# Sheet1_3big.net
KiCad netlist of a schematic drawn in Altium Designer
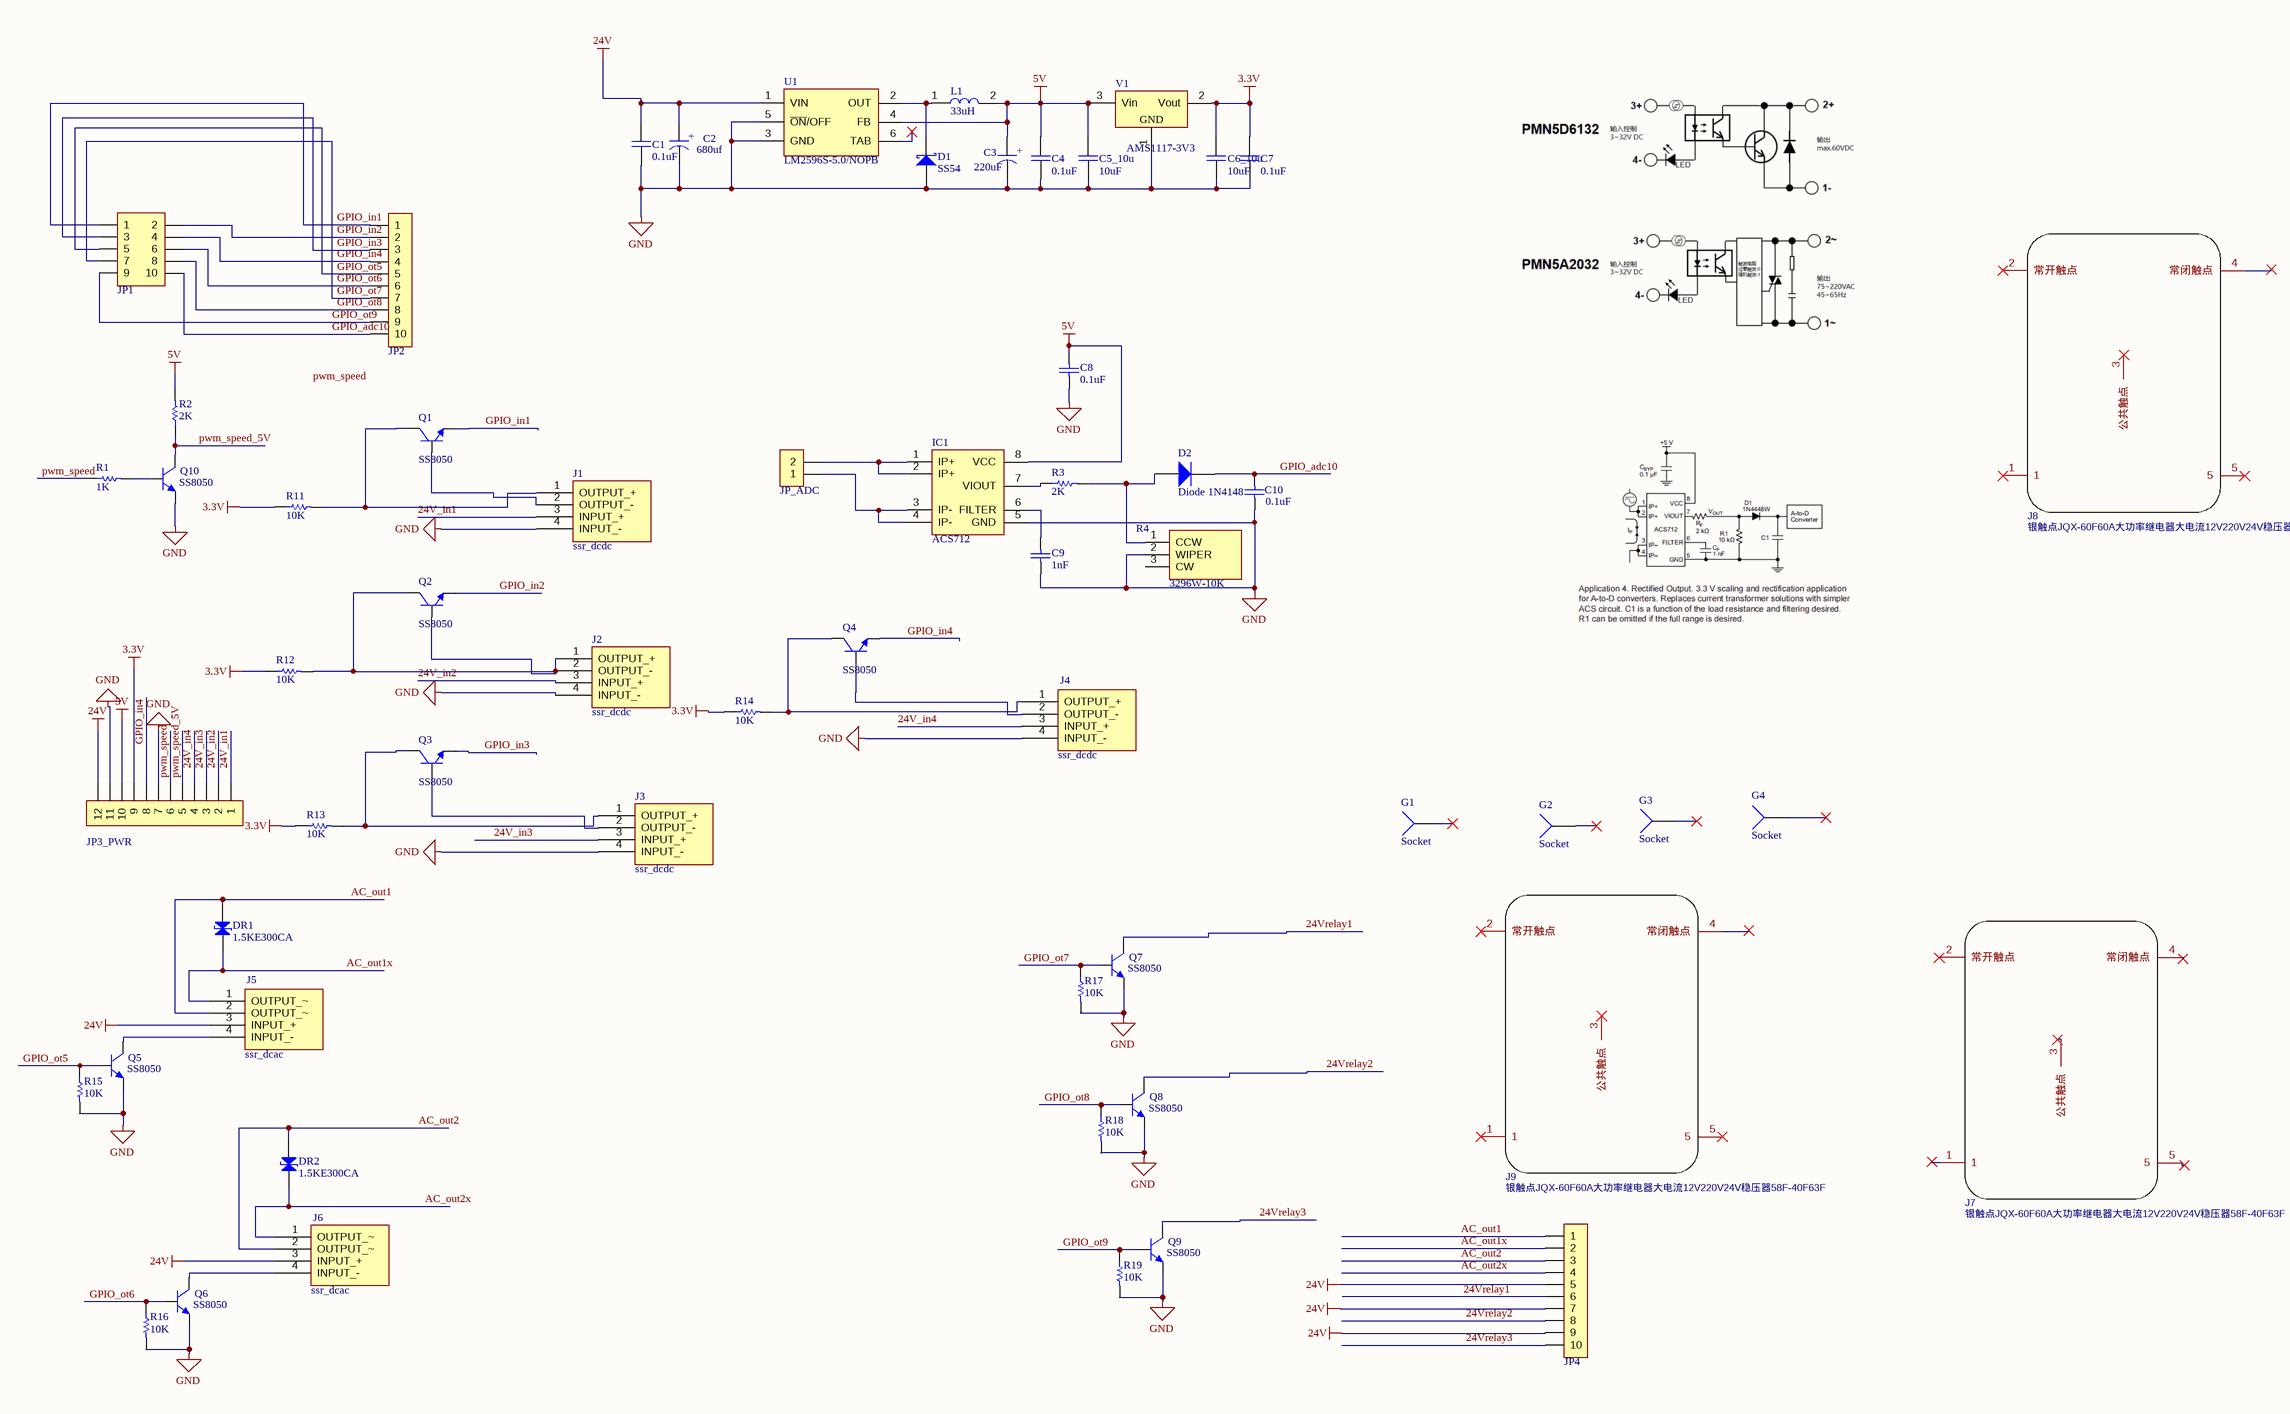
[diagram p0: Sheet1_3big.SchDoc]

(export (version "E")
  (design (tool "Eeschema 10.0.6"))
  (components
    (comp (ref "C1") (value "0.1uF") (footprint "C 0805_M") (libsource (lib "LM2596S_5.0") (part "CAP-SMT")))
    (comp (ref "C2")
      (value "680uf")
      (footprint "CAP 5.0*12.5*20")
      (description "CAP-SMD")
      (libsource (lib "LM2596S_5.0") (part "CAP-SMD"))
    )
    (comp (ref "C3")
      (value "220uF")
      (footprint "CAP 5.0*10*16")
      (description "CAP-SMD")
      (libsource (lib "LM2596S_5.0") (part "CAP-SMD"))
    )
    (comp (ref "C4") (value "0.1uF") (footprint "C 0805_M") (libsource (lib "LM2596S_5.0") (part "CAP-SMT")))
    (comp (ref "C5_10u")
      (value "10uF")
      (footprint "C 0805_M")
      (libsource (lib "LM2596S_5.0") (part "CAP-SMT"))
    )
    (comp (ref "C6_10u")
      (value "10uF")
      (footprint "C 0805_M")
      (libsource (lib "LM2596S_5.0") (part "CAP-SMT"))
    )
    (comp (ref "C7") (value "0.1uF") (footprint "C 0805_M") (libsource (lib "LM2596S_5.0") (part "CAP-SMT")))
    (comp (ref "C8")
      (value "0.1uF")
      (footprint "C 0805_M")
      (description "Capacitor")
      (fields (field (name "PUBLISHER") "Altium Limited"))
      (libsource (lib "Miscellaneous Devices") (part "Cap"))
    )
    (comp (ref "C9")
      (value "1nF")
      (footprint "C 0805_M")
      (description "Capacitor")
      (fields (field (name "PUBLISHER") "Altium Limited"))
      (libsource (lib "Miscellaneous Devices") (part "Cap"))
    )
    (comp (ref "C10")
      (value "0.1uF")
      (footprint "C 0805_M")
      (description "Capacitor")
      (fields (field (name "PUBLISHER") "Altium Limited"))
      (libsource (lib "Miscellaneous Devices") (part "Cap"))
    )
    (comp (ref "D1") (value "SS54") (footprint "SMA") (libsource (lib "LM2596S_5.0") (part "DIO")))
    (comp (ref "D2")
      (value "Diode 1N4148")
      (footprint "SOD-123")
      (description "High Conductance Fast Diode")
      (fields (field (name "PUBLISHER") "Altium Limited"))
      (libsource (lib "Miscellaneous Devices") (part "Diode 1N4148"))
    )
    (comp (ref "DR1")
      (value "1.5KE300CA")
      (footprint "SMB_L4.6-W3.6-LS5.3-BI")
      (description "瞬态电压抑制二极管")
      (fields (field (name "版权归属") "源创客"))
      (libsource (lib "8.1   - 二极管-整流桥") (part "DR"))
    )
    (comp (ref "DR2")
      (value "1.5KE300CA")
      (footprint "SMB_L4.6-W3.6-LS5.3-BI")
      (description "瞬态电压抑制二极管")
      (fields (field (name "版权归属") "源创客"))
      (libsource (lib "8.1   - 二极管-整流桥") (part "DR"))
    )
    (comp (ref "G1")
      (value "Socket")
      (footprint "M3x6_L")
      (fields (field (name "PUBLISHER") "Altium Limited"))
      (libsource (lib "Miscellaneous Connectors") (part "Socket"))
    )
    (comp (ref "G2")
      (value "Socket")
      (footprint "M3x6_L")
      (fields (field (name "PUBLISHER") "Altium Limited"))
      (libsource (lib "Miscellaneous Connectors") (part "Socket"))
    )
    (comp (ref "G3")
      (value "Socket")
      (footprint "M3x6_L")
      (fields (field (name "PUBLISHER") "Altium Limited"))
      (libsource (lib "Miscellaneous Connectors") (part "Socket"))
    )
    (comp (ref "G4")
      (value "Socket")
      (footprint "M3x6_L")
      (fields (field (name "PUBLISHER") "Altium Limited"))
      (libsource (lib "Miscellaneous Connectors") (part "Socket"))
    )
    (comp (ref "IC1")
      (value "ACS712")
      (footprint "SOP8_M")
      (description "电流检测芯片")
      (fields (field (name "版权归属") "源创客"))
      (libsource (lib "1.1   - IC芯片") (part "ACS712"))
    )
    (comp (ref "J1")
      (value "ssr_dcdc")
      (footprint "2982647")
      (description "Connector")
      (fields
        (field (name "MANUFACTURER_PART_NUMBER") "2982647")
        (field (name "MOUSER PART NUMBER") "651-2982647")
      )
      (libsource (lib "") (part "ssr_dcdc_1"))
    )
    (comp (ref "J2")
      (value "ssr_dcdc")
      (footprint "2982647")
      (description "Connector")
      (fields
        (field (name "MANUFACTURER_PART_NUMBER") "2982647")
        (field (name "MOUSER PART NUMBER") "651-2982647")
      )
      (libsource (lib "") (part "ssr_dcdc_1"))
    )
    (comp (ref "J3")
      (value "ssr_dcdc")
      (footprint "2982647")
      (description "Connector")
      (fields
        (field (name "MANUFACTURER_PART_NUMBER") "2982647")
        (field (name "MOUSER PART NUMBER") "651-2982647")
      )
      (libsource (lib "") (part "ssr_dcdc_1"))
    )
    (comp (ref "J4")
      (value "ssr_dcdc")
      (footprint "SamacSys:SSR_DCDC")
      (description "Connector")
      (fields
        (field (name "MANUFACTURER_PART_NUMBER") "2982647")
        (field (name "MOUSER PART NUMBER") "651-2982647")
      )
      (libsource (lib "SamacSys") (part "ssr_dcdc"))
    )
    (comp (ref "J5")
      (value "ssr_dcac")
      (footprint "SSR_DCAC")
      (description "Connector")
      (fields
        (field (name "MANUFACTURER_PART_NUMBER") "2982647")
        (field (name "MOUSER PART NUMBER") "651-2982647")
      )
      (libsource (lib "SamacSys") (part "ssr_dcac"))
    )
    (comp (ref "J6")
      (value "ssr_dcac")
      (footprint "SSR_DCAC")
      (description "Connector")
      (fields
        (field (name "MANUFACTURER_PART_NUMBER") "2982647")
        (field (name "MOUSER PART NUMBER") "651-2982647")
      )
      (libsource (lib "SamacSys") (part "ssr_dcac"))
    )
    (comp (ref "J7")
      (value "银触点JQX-60F60A大功率继电器大电流12V220V24V稳压器58F-40F63F")
      (footprint "24V_Big_Relay")
      (fields (field (name "CONTRIBUTOR") "locolyl"))
      (libsource (lib "altium-import") (part "root_0_银触点JQX-60F60A大功率继电器大电流12V220V24V稳压器58F-40F63F_"))
    )
    (comp (ref "J8")
      (value "银触点JQX-60F60A大功率继电器大电流12V220V24V稳压器58F-40F63F")
      (footprint "24V_Big_Relay")
      (fields (field (name "CONTRIBUTOR") "locolyl"))
      (libsource (lib "altium-import") (part "root_0_银触点JQX-60F60A大功率继电器大电流12V220V24V稳压器58F-40F63F_"))
    )
    (comp (ref "J9")
      (value "银触点JQX-60F60A大功率继电器大电流12V220V24V稳压器58F-40F63F")
      (footprint "24V_Big_Relay")
      (fields (field (name "CONTRIBUTOR") "locolyl"))
      (libsource (lib "altium-import") (part "root_0_银触点JQX-60F60A大功率继电器大电流12V220V24V稳压器58F-40F63F_"))
    )
    (comp (ref "JP1")
      (value "Header 5X2")
      (footprint "IDC2.54-LI-2x5P")
      (description "5*2P接插件")
      (fields (field (name "版权归属") "源创客"))
      (libsource (lib "4.5   - 接插件-脚距2.54") (part "Header 5X2"))
    )
    (comp (ref "JP2")
      (value "HDR-1X10")
      (footprint "KF128-3.81-10P")
      (description "10P接插件")
      (fields (field (name "版权归属") "源创客"))
      (libsource (lib "4.6   - 接插件-脚距3.5") (part "Header 10"))
    )
    (comp (ref "JP3_PWR")
      (value "HDR-1X12")
      (footprint "KF128-3.81-12P")
      (description "12P接插件")
      (fields (field (name "版权归属") "源创客"))
      (libsource (lib "4.7   - 接插件-脚距3.81") (part "Header 12"))
    )
    (comp (ref "JP4")
      (value "HDR-1X10")
      (footprint "KF128-3.81-10P")
      (description "10P接插件")
      (fields (field (name "版权归属") "源创客"))
      (libsource (lib "4.6   - 接插件-脚距3.5") (part "Header 10"))
    )
    (comp (ref "JP_ADC")
      (value "HDR-1X2")
      (footprint "KF128-3.81-2P")
      (description "2P接插件")
      (fields (field (name "版权归属") "源创客"))
      (libsource (lib "4.7   - 接插件-脚距3.81") (part "Header 2"))
    )
    (comp (ref "L1") (value "33uH") (footprint "CDRH74") (libsource (lib "LM2596S_5.0") (part "L-CDRH74")))
    (comp (ref "Q1")
      (value "SS8050")
      (footprint "TO92A")
      (description "高频放大-NPN型")
      (fields (field (name "版权归属") "源创客"))
      (libsource (lib "6.2   - 三极管") (part "8050-DIP"))
    )
    (comp (ref "Q2")
      (value "SS8050")
      (footprint "TO92A")
      (description "高频放大-NPN型")
      (fields (field (name "版权归属") "源创客"))
      (libsource (lib "6.2   - 三极管") (part "8050-DIP"))
    )
    (comp (ref "Q3")
      (value "SS8050")
      (footprint "TO92A")
      (description "高频放大-NPN型")
      (fields (field (name "版权归属") "源创客"))
      (libsource (lib "6.2   - 三极管") (part "8050-DIP"))
    )
    (comp (ref "Q4")
      (value "SS8050")
      (footprint "TO92A")
      (description "高频放大-NPN型")
      (fields (field (name "版权归属") "源创客"))
      (libsource (lib "6.2   - 三极管") (part "8050-DIP"))
    )
    (comp (ref "Q5")
      (value "SS8050")
      (footprint "TO92A")
      (description "高频放大-NPN型")
      (fields (field (name "版权归属") "源创客"))
      (libsource (lib "6.2   - 三极管") (part "8050-DIP"))
    )
    (comp (ref "Q6")
      (value "SS8050")
      (footprint "TO92A")
      (description "高频放大-NPN型")
      (fields (field (name "版权归属") "源创客"))
      (libsource (lib "6.2   - 三极管") (part "8050-DIP"))
    )
    (comp (ref "Q7")
      (value "SS8050")
      (footprint "TO92A")
      (description "高频放大-NPN型")
      (fields (field (name "版权归属") "源创客"))
      (libsource (lib "6.2   - 三极管") (part "8050-DIP"))
    )
    (comp (ref "Q8")
      (value "SS8050")
      (footprint "TO92A")
      (description "高频放大-NPN型")
      (fields (field (name "版权归属") "源创客"))
      (libsource (lib "6.2   - 三极管") (part "8050-DIP"))
    )
    (comp (ref "Q9")
      (value "SS8050")
      (footprint "TO92A")
      (description "高频放大-NPN型")
      (fields (field (name "版权归属") "源创客"))
      (libsource (lib "6.2   - 三极管") (part "8050-DIP"))
    )
    (comp (ref "Q10")
      (value "SS8050")
      (footprint "TO92A")
      (description "高频放大-NPN型")
      (fields (field (name "版权归属") "源创客"))
      (libsource (lib "6.2   - 三极管") (part "8050-DIP"))
    )
    (comp (ref "R1")
      (value "1K")
      (footprint "R 0805_M")
      (description "Resistor")
      (fields (field (name "PUBLISHER") "Altium Limited"))
      (libsource (lib "Miscellaneous Devices") (part "Res1"))
    )
    (comp (ref "R2")
      (value "2K")
      (footprint "R 0805_M")
      (description "Resistor")
      (fields (field (name "PUBLISHER") "Altium Limited"))
      (libsource (lib "Miscellaneous Devices") (part "Res1"))
    )
    (comp (ref "R3")
      (value "2K")
      (footprint "R 0805_M")
      (description "Resistor")
      (fields (field (name "PUBLISHER") "Altium Limited"))
      (libsource (lib "Miscellaneous Devices") (part "Res1"))
    )
    (comp (ref "R4")
      (value "3296W-10K")
      (footprint "3296W")
      (description "Resistor")
      (fields
        (field (name "MANUFACTURER_PART_NUMBER") "3296W-1-100LF")
        (field (name "MOUSER PART NUMBER") "652-3296W-1-100LF")
      )
      (libsource (lib "*") (part "3296W-1-100LF"))
    )
    (comp (ref "R11")
      (value "10K")
      (footprint "R 0805_M")
      (description "Resistor")
      (fields (field (name "PUBLISHER") "Altium Limited"))
      (libsource (lib "Miscellaneous Devices") (part "Res1"))
    )
    (comp (ref "R12")
      (value "10K")
      (footprint "R 0805_M")
      (description "Resistor")
      (fields (field (name "PUBLISHER") "Altium Limited"))
      (libsource (lib "Miscellaneous Devices") (part "Res1"))
    )
    (comp (ref "R13")
      (value "10K")
      (footprint "R 0805_M")
      (description "Resistor")
      (fields (field (name "PUBLISHER") "Altium Limited"))
      (libsource (lib "Miscellaneous Devices") (part "Res1"))
    )
    (comp (ref "R14")
      (value "10K")
      (footprint "R 0805_M")
      (description "Resistor")
      (fields (field (name "PUBLISHER") "Altium Limited"))
      (libsource (lib "Miscellaneous Devices") (part "Res1"))
    )
    (comp (ref "R15")
      (value "10K")
      (footprint "R 0805_M")
      (description "Resistor")
      (fields (field (name "PUBLISHER") "Altium Limited"))
      (libsource (lib "Miscellaneous Devices") (part "Res1"))
    )
    (comp (ref "R16")
      (value "10K")
      (footprint "R 0805_M")
      (description "Resistor")
      (fields (field (name "PUBLISHER") "Altium Limited"))
      (libsource (lib "Miscellaneous Devices") (part "Res1"))
    )
    (comp (ref "R17")
      (value "10K")
      (footprint "R 0805_M")
      (description "Resistor")
      (fields (field (name "PUBLISHER") "Altium Limited"))
      (libsource (lib "Miscellaneous Devices") (part "Res1"))
    )
    (comp (ref "R18")
      (value "10K")
      (footprint "R 0805_M")
      (description "Resistor")
      (fields (field (name "PUBLISHER") "Altium Limited"))
      (libsource (lib "Miscellaneous Devices") (part "Res1"))
    )
    (comp (ref "R19")
      (value "10K")
      (footprint "R 0805_M")
      (description "Resistor")
      (fields (field (name "PUBLISHER") "Altium Limited"))
      (libsource (lib "Miscellaneous Devices") (part "Res1"))
    )
    (comp (ref "U1")
      (value "LM2596S-5.0/NOPB")
      (footprint "TO263-5A")
      (description "SIMPLE SWITCHER® Power Converter 150 KHz 3A Step-Down Voltage Regulator, 5-pin TO-263, Pb-Free")
      (fields (field (name "MANUFACTURER") "Texas Instruments"))
      (libsource (lib "LM2596S_5.0") (part "LM2596S-5.0"))
    )
    (comp (ref "V1")
      (value "AMS1117-3V3")
      (footprint "SOT223_M")
      (description "三端稳压芯片")
      (fields (field (name "版权归属") "源创客"))
      (libsource (lib "1.3   - 电源类芯片") (part "AMS1117"))
    )
  )
  (nets
    (net (code "1") (name "/24V_in1") (class "Default")
      (node (ref "J1") (pin "3") (pinfunction "INPUT_+_3") (pintype "passive"))
      (node (ref "JP3_PWR") (pin "1") (pinfunction "1_1") (pintype "passive"))
    )
    (net (code "2") (name "/24V_in2") (class "Default")
      (node (ref "J2") (pin "3") (pinfunction "INPUT_+_3") (pintype "passive"))
      (node (ref "JP3_PWR") (pin "2") (pinfunction "2_2") (pintype "passive"))
    )
    (net (code "3") (name "/24V_in3") (class "Default")
      (node (ref "J3") (pin "3") (pinfunction "INPUT_+_3") (pintype "passive"))
      (node (ref "JP3_PWR") (pin "3") (pinfunction "3_3") (pintype "passive"))
    )
    (net (code "4") (name "/24V_in4") (class "Default")
      (node (ref "J4") (pin "3") (pinfunction "INPUT_+_3") (pintype "passive"))
      (node (ref "JP3_PWR") (pin "4") (pinfunction "4_4") (pintype "passive"))
    )
    (net (code "5") (name "/24Vrelay1") (class "Default")
      (node (ref "JP4") (pin "6") (pinfunction "6_6") (pintype "passive"))
      (node (ref "Q7") (pin "3") (pinfunction "C_3") (pintype "passive"))
    )
    (net (code "6") (name "/24Vrelay2") (class "Default")
      (node (ref "JP4") (pin "8") (pinfunction "8_8") (pintype "passive"))
      (node (ref "Q8") (pin "3") (pinfunction "C_3") (pintype "passive"))
    )
    (net (code "7") (name "/24Vrelay3") (class "Default")
      (node (ref "JP4") (pin "10") (pinfunction "10_10") (pintype "passive"))
      (node (ref "Q9") (pin "3") (pinfunction "C_3") (pintype "passive"))
    )
    (net (code "8") (name "/AC_out1") (class "Default")
      (node (ref "DR1") (pin "1") (pinfunction "A_1") (pintype "passive"))
      (node (ref "J5") (pin "2") (pinfunction "OUTPUT_~_2") (pintype "passive"))
      (node (ref "JP4") (pin "1") (pinfunction "1_1") (pintype "passive"))
    )
    (net (code "9") (name "/AC_out1x") (class "Default")
      (node (ref "DR1") (pin "2") (pinfunction "K_2") (pintype "passive"))
      (node (ref "J5") (pin "1") (pinfunction "OUTPUT_~_1") (pintype "passive"))
      (node (ref "JP4") (pin "2") (pinfunction "2_2") (pintype "passive"))
    )
    (net (code "10") (name "/AC_out2") (class "Default")
      (node (ref "DR2") (pin "1") (pinfunction "A_1") (pintype "passive"))
      (node (ref "J6") (pin "2") (pinfunction "OUTPUT_~_2") (pintype "passive"))
      (node (ref "JP4") (pin "3") (pinfunction "3_3") (pintype "passive"))
    )
    (net (code "11") (name "/AC_out2x") (class "Default")
      (node (ref "DR2") (pin "2") (pinfunction "K_2") (pintype "passive"))
      (node (ref "J6") (pin "1") (pinfunction "OUTPUT_~_1") (pintype "passive"))
      (node (ref "JP4") (pin "4") (pinfunction "4_4") (pintype "passive"))
    )
    (net (code "12") (name "/GPIO_adc10") (class "Default")
      (node (ref "C10") (pin "2") (pinfunction "2_2") (pintype "passive"))
      (node (ref "D2") (pin "2") (pinfunction "K_2") (pintype "passive"))
      (node (ref "JP1") (pin "10") (pinfunction "10_10") (pintype "passive"))
      (node (ref "JP2") (pin "10") (pinfunction "10_10") (pintype "passive"))
    )
    (net (code "13") (name "/GPIO_in1") (class "Default")
      (node (ref "JP1") (pin "1") (pinfunction "1_1") (pintype "passive"))
      (node (ref "JP2") (pin "1") (pinfunction "1_1") (pintype "passive"))
      (node (ref "Q1") (pin "1") (pinfunction "E_1") (pintype "passive"))
    )
    (net (code "14") (name "/GPIO_in2") (class "Default")
      (node (ref "JP1") (pin "2") (pinfunction "2_2") (pintype "passive"))
      (node (ref "JP2") (pin "2") (pinfunction "2_2") (pintype "passive"))
      (node (ref "Q2") (pin "1") (pinfunction "E_1") (pintype "passive"))
    )
    (net (code "15") (name "/GPIO_in3") (class "Default")
      (node (ref "JP1") (pin "3") (pinfunction "3_3") (pintype "passive"))
      (node (ref "JP2") (pin "3") (pinfunction "3_3") (pintype "passive"))
      (node (ref "Q3") (pin "1") (pinfunction "E_1") (pintype "passive"))
    )
    (net (code "16") (name "/GPIO_in4") (class "Default")
      (node (ref "JP1") (pin "4") (pinfunction "4_4") (pintype "passive"))
      (node (ref "JP2") (pin "4") (pinfunction "4_4") (pintype "passive"))
      (node (ref "JP3_PWR") (pin "8") (pinfunction "8_8") (pintype "passive"))
      (node (ref "Q4") (pin "1") (pinfunction "E_1") (pintype "passive"))
    )
    (net (code "17") (name "/GPIO_ot5") (class "Default")
      (node (ref "JP1") (pin "5") (pinfunction "5_5") (pintype "passive"))
      (node (ref "JP2") (pin "5") (pinfunction "5_5") (pintype "passive"))
      (node (ref "Q5") (pin "2") (pinfunction "B_2") (pintype "passive"))
      (node (ref "R15") (pin "1") (pinfunction "1_1") (pintype "passive"))
    )
    (net (code "18") (name "/GPIO_ot6") (class "Default")
      (node (ref "JP1") (pin "6") (pinfunction "6_6") (pintype "passive"))
      (node (ref "JP2") (pin "6") (pinfunction "6_6") (pintype "passive"))
      (node (ref "Q6") (pin "2") (pinfunction "B_2") (pintype "passive"))
      (node (ref "R16") (pin "1") (pinfunction "1_1") (pintype "passive"))
    )
    (net (code "19") (name "/GPIO_ot7") (class "Default")
      (node (ref "JP1") (pin "7") (pinfunction "7_7") (pintype "passive"))
      (node (ref "JP2") (pin "7") (pinfunction "7_7") (pintype "passive"))
      (node (ref "Q7") (pin "2") (pinfunction "B_2") (pintype "passive"))
      (node (ref "R17") (pin "1") (pinfunction "1_1") (pintype "passive"))
    )
    (net (code "20") (name "/GPIO_ot8") (class "Default")
      (node (ref "JP1") (pin "8") (pinfunction "8_8") (pintype "passive"))
      (node (ref "JP2") (pin "8") (pinfunction "8_8") (pintype "passive"))
      (node (ref "Q8") (pin "2") (pinfunction "B_2") (pintype "passive"))
      (node (ref "R18") (pin "1") (pinfunction "1_1") (pintype "passive"))
    )
    (net (code "21") (name "/GPIO_ot9") (class "Default")
      (node (ref "JP1") (pin "9") (pinfunction "9_9") (pintype "passive"))
      (node (ref "JP2") (pin "9") (pinfunction "9_9") (pintype "passive"))
      (node (ref "Q9") (pin "2") (pinfunction "B_2") (pintype "passive"))
      (node (ref "R19") (pin "1") (pinfunction "1_1") (pintype "passive"))
    )
    (net (code "22") (name "/pwm_speed") (class "Default")
      (node (ref "JP3_PWR") (pin "6") (pinfunction "6_6") (pintype "passive"))
      (node (ref "R1") (pin "1") (pinfunction "1_1") (pintype "passive"))
    )
    (net (code "23") (name "/pwm_speed_5V") (class "Default")
      (node (ref "JP3_PWR") (pin "5") (pinfunction "5_5") (pintype "passive"))
      (node (ref "Q10") (pin "3") (pinfunction "C_3") (pintype "passive"))
      (node (ref "R2") (pin "1") (pinfunction "1_1") (pintype "passive"))
    )
    (net (code "24") (name "3.3V") (class "Default")
      (node (ref "C6_10u") (pin "2") (pinfunction "2_2") (pintype "passive"))
      (node (ref "C7") (pin "2") (pinfunction "2_2") (pintype "passive"))
      (node (ref "JP3_PWR") (pin "9") (pinfunction "9_9") (pintype "passive"))
      (node (ref "R11") (pin "1") (pinfunction "1_1") (pintype "passive"))
      (node (ref "R12") (pin "1") (pinfunction "1_1") (pintype "passive"))
      (node (ref "R13") (pin "1") (pinfunction "1_1") (pintype "passive"))
      (node (ref "R14") (pin "1") (pinfunction "1_1") (pintype "passive"))
      (node (ref "V1") (pin "2") (pinfunction "Vout_2") (pintype "passive"))
    )
    (net (code "25") (name "5V") (class "Default")
      (node (ref "C3") (pin "2") (pinfunction "2_2") (pintype "passive"))
      (node (ref "C4") (pin "2") (pinfunction "2_2") (pintype "passive"))
      (node (ref "C5_10u") (pin "2") (pinfunction "2_2") (pintype "passive"))
      (node (ref "C8") (pin "2") (pinfunction "2_2") (pintype "passive"))
      (node (ref "IC1") (pin "8") (pinfunction "VCC_8") (pintype "passive"))
      (node (ref "JP3_PWR") (pin "10") (pinfunction "10_10") (pintype "passive"))
      (node (ref "L1") (pin "2") (pinfunction "2_2") (pintype "passive"))
      (node (ref "R2") (pin "2") (pinfunction "2_2") (pintype "passive"))
      (node (ref "U1") (pin "4") (pinfunction "FB_4") (pintype "passive"))
      (node (ref "V1") (pin "3") (pinfunction "Vin_3") (pintype "passive"))
    )
    (net (code "26") (name "24V") (class "Default")
      (node (ref "C1") (pin "2") (pinfunction "2_2") (pintype "passive"))
      (node (ref "C2") (pin "2") (pinfunction "2_2") (pintype "passive"))
      (node (ref "J5") (pin "3") (pinfunction "INPUT_+_3") (pintype "passive"))
      (node (ref "J6") (pin "3") (pinfunction "INPUT_+_3") (pintype "passive"))
      (node (ref "JP3_PWR") (pin "12") (pinfunction "12_12") (pintype "passive"))
      (node (ref "JP4") (pin "5") (pinfunction "5_5") (pintype "passive"))
      (node (ref "JP4") (pin "7") (pinfunction "7_7") (pintype "passive"))
      (node (ref "JP4") (pin "9") (pinfunction "9_9") (pintype "passive"))
      (node (ref "U1") (pin "1") (pinfunction "VIN_1") (pintype "power_in"))
    )
    (net (code "27") (name "GND") (class "Default")
      (node (ref "C1") (pin "1") (pinfunction "1_1") (pintype "passive"))
      (node (ref "C10") (pin "1") (pinfunction "1_1") (pintype "passive"))
      (node (ref "C2") (pin "1") (pinfunction "1_1") (pintype "passive"))
      (node (ref "C3") (pin "1") (pinfunction "1_1") (pintype "passive"))
      (node (ref "C4") (pin "1") (pinfunction "1_1") (pintype "passive"))
      (node (ref "C5_10u") (pin "1") (pinfunction "1_1") (pintype "passive"))
      (node (ref "C6_10u") (pin "1") (pinfunction "1_1") (pintype "passive"))
      (node (ref "C7") (pin "1") (pinfunction "1_1") (pintype "passive"))
      (node (ref "C8") (pin "1") (pinfunction "1_1") (pintype "passive"))
      (node (ref "C9") (pin "1") (pinfunction "1_1") (pintype "passive"))
      (node (ref "D1") (pin "1") (pinfunction "1_1") (pintype "passive"))
      (node (ref "IC1") (pin "5") (pinfunction "GND_5") (pintype "passive"))
      (node (ref "J1") (pin "4") (pinfunction "INPUT_-_4") (pintype "passive"))
      (node (ref "J2") (pin "4") (pinfunction "INPUT_-_4") (pintype "passive"))
      (node (ref "J3") (pin "4") (pinfunction "INPUT_-_4") (pintype "passive"))
      (node (ref "J4") (pin "4") (pinfunction "INPUT_-_4") (pintype "passive"))
      (node (ref "JP3_PWR") (pin "11") (pinfunction "11_11") (pintype "passive"))
      (node (ref "JP3_PWR") (pin "7") (pinfunction "7_7") (pintype "passive"))
      (node (ref "Q10") (pin "1") (pinfunction "E_1") (pintype "passive"))
      (node (ref "Q5") (pin "1") (pinfunction "E_1") (pintype "passive"))
      (node (ref "Q6") (pin "1") (pinfunction "E_1") (pintype "passive"))
      (node (ref "Q7") (pin "1") (pinfunction "E_1") (pintype "passive"))
      (node (ref "Q8") (pin "1") (pinfunction "E_1") (pintype "passive"))
      (node (ref "Q9") (pin "1") (pinfunction "E_1") (pintype "passive"))
      (node (ref "R15") (pin "2") (pinfunction "2_2") (pintype "passive"))
      (node (ref "R16") (pin "2") (pinfunction "2_2") (pintype "passive"))
      (node (ref "R17") (pin "2") (pinfunction "2_2") (pintype "passive"))
      (node (ref "R18") (pin "2") (pinfunction "2_2") (pintype "passive"))
      (node (ref "R19") (pin "2") (pinfunction "2_2") (pintype "passive"))
      (node (ref "R4") (pin "2") (pinfunction "WIPER_2") (pintype "passive"))
      (node (ref "U1") (pin "3") (pinfunction "GND_3") (pintype "power_in"))
      (node (ref "U1") (pin "5") (pinfunction "~{ON}/OFF_5") (pintype "passive"))
      (node (ref "V1") (pin "1") (pinfunction "GND_1") (pintype "passive"))
    )
    (net (code "28") (name "Net-(D2-A)") (class "Default")
      (node (ref "D2") (pin "1") (pinfunction "A_1") (pintype "passive"))
      (node (ref "R3") (pin "2") (pinfunction "2_2") (pintype "passive"))
      (node (ref "R4") (pin "1") (pinfunction "CCW_1") (pintype "passive"))
    )
    (net (code "29") (name "Net-(IC1-FILTER)") (class "Default")
      (node (ref "C9") (pin "2") (pinfunction "2_2") (pintype "passive"))
      (node (ref "IC1") (pin "6") (pinfunction "FILTER_6") (pintype "passive"))
    )
    (net (code "30") (name "Net-(IC1-IP+-Pad1)") (class "Default")
      (node (ref "IC1") (pin "1") (pinfunction "IP+_1") (pintype "passive"))
      (node (ref "IC1") (pin "2") (pinfunction "IP+_2") (pintype "passive"))
      (node (ref "JP_ADC") (pin "2") (pinfunction "2_2") (pintype "passive"))
    )
    (net (code "31") (name "Net-(IC1-IP--Pad3)") (class "Default")
      (node (ref "IC1") (pin "3") (pinfunction "IP-_3") (pintype "passive"))
      (node (ref "IC1") (pin "4") (pinfunction "IP-_4") (pintype "passive"))
      (node (ref "JP_ADC") (pin "1") (pinfunction "1_1") (pintype "passive"))
    )
    (net (code "32") (name "Net-(IC1-VIOUT)") (class "Default")
      (node (ref "IC1") (pin "7") (pinfunction "VIOUT_7") (pintype "passive"))
      (node (ref "R3") (pin "1") (pinfunction "1_1") (pintype "passive"))
    )
    (net (code "33") (name "Net-(J1-OUTPUT_+)") (class "Default")
      (node (ref "J1") (pin "1") (pinfunction "OUTPUT_+_1") (pintype "passive"))
      (node (ref "Q1") (pin "3") (pinfunction "C_3") (pintype "passive"))
      (node (ref "R11") (pin "2") (pinfunction "2_2") (pintype "passive"))
    )
    (net (code "34") (name "Net-(J1-OUTPUT_-)") (class "Default")
      (node (ref "J1") (pin "2") (pinfunction "OUTPUT_-_2") (pintype "passive"))
      (node (ref "Q1") (pin "2") (pinfunction "B_2") (pintype "passive"))
    )
    (net (code "35") (name "Net-(J2-OUTPUT_+)") (class "Default")
      (node (ref "J2") (pin "1") (pinfunction "OUTPUT_+_1") (pintype "passive"))
      (node (ref "J2") (pin "2") (pinfunction "OUTPUT_-_2") (pintype "passive"))
      (node (ref "Q2") (pin "2") (pinfunction "B_2") (pintype "passive"))
      (node (ref "Q2") (pin "3") (pinfunction "C_3") (pintype "passive"))
      (node (ref "R12") (pin "2") (pinfunction "2_2") (pintype "passive"))
    )
    (net (code "36") (name "Net-(J3-OUTPUT_+)") (class "Default")
      (node (ref "J3") (pin "1") (pinfunction "OUTPUT_+_1") (pintype "passive"))
      (node (ref "Q3") (pin "3") (pinfunction "C_3") (pintype "passive"))
      (node (ref "R13") (pin "2") (pinfunction "2_2") (pintype "passive"))
    )
    (net (code "37") (name "Net-(J3-OUTPUT_-)") (class "Default")
      (node (ref "J3") (pin "2") (pinfunction "OUTPUT_-_2") (pintype "passive"))
      (node (ref "Q3") (pin "2") (pinfunction "B_2") (pintype "passive"))
    )
    (net (code "38") (name "Net-(J4-OUTPUT_+)") (class "Default")
      (node (ref "J4") (pin "1") (pinfunction "OUTPUT_+_1") (pintype "passive"))
      (node (ref "Q4") (pin "3") (pinfunction "C_3") (pintype "passive"))
      (node (ref "R14") (pin "2") (pinfunction "2_2") (pintype "passive"))
    )
    (net (code "39") (name "Net-(J4-OUTPUT_-)") (class "Default")
      (node (ref "J4") (pin "2") (pinfunction "OUTPUT_-_2") (pintype "passive"))
      (node (ref "Q4") (pin "2") (pinfunction "B_2") (pintype "passive"))
    )
    (net (code "40") (name "Net-(J5-INPUT_-)") (class "Default")
      (node (ref "J5") (pin "4") (pinfunction "INPUT_-_4") (pintype "passive"))
      (node (ref "Q5") (pin "3") (pinfunction "C_3") (pintype "passive"))
    )
    (net (code "41") (name "Net-(J6-INPUT_-)") (class "Default")
      (node (ref "J6") (pin "4") (pinfunction "INPUT_-_4") (pintype "passive"))
      (node (ref "Q6") (pin "3") (pinfunction "C_3") (pintype "passive"))
    )
    (net (code "42") (name "Net-(Q10-B)") (class "Default")
      (node (ref "Q10") (pin "2") (pinfunction "B_2") (pintype "passive"))
      (node (ref "R1") (pin "2") (pinfunction "2_2") (pintype "passive"))
    )
    (net (code "43") (name "Net-(U1-OUT)") (class "Default")
      (node (ref "D1") (pin "2") (pinfunction "2_2") (pintype "passive"))
      (node (ref "L1") (pin "1") (pinfunction "1_1") (pintype "passive"))
      (node (ref "U1") (pin "2") (pinfunction "OUT_2") (pintype "power_in"))
    )
    (net (code "44") (name "unconnected-(G1-Pad1)") (class "Default")
      (node (ref "G1") (pin "1") (pinfunction "1_1") (pintype "passive+no_connect"))
    )
    (net (code "45") (name "unconnected-(G2-Pad1)") (class "Default")
      (node (ref "G2") (pin "1") (pinfunction "1_1") (pintype "passive+no_connect"))
    )
    (net (code "46") (name "unconnected-(G3-Pad1)") (class "Default")
      (node (ref "G3") (pin "1") (pinfunction "1_1") (pintype "passive+no_connect"))
    )
    (net (code "47") (name "unconnected-(G4-Pad1)") (class "Default")
      (node (ref "G4") (pin "1") (pinfunction "1_1") (pintype "passive+no_connect"))
    )
    (net (code "48") (name "unconnected-(J7-Pad1)") (class "Default")
      (node (ref "J7") (pin "1") (pinfunction "1_1") (pintype "passive+no_connect"))
    )
    (net (code "49") (name "unconnected-(J7-Pad5)") (class "Default")
      (node (ref "J7") (pin "5") (pinfunction "5_5") (pintype "passive+no_connect"))
    )
    (net (code "50") (name "unconnected-(J7-公共触点-Pad3)") (class "Default")
      (node (ref "J7") (pin "3") (pinfunction "公共触点_3") (pintype "passive+no_connect"))
    )
    (net (code "51") (name "unconnected-(J7-常开触点-Pad2)") (class "Default")
      (node (ref "J7") (pin "2") (pinfunction "常开触点_2") (pintype "passive+no_connect"))
    )
    (net (code "52") (name "unconnected-(J7-常闭触点-Pad4)") (class "Default")
      (node (ref "J7") (pin "4") (pinfunction "常闭触点_4") (pintype "passive+no_connect"))
    )
    (net (code "53") (name "unconnected-(J8-Pad1)") (class "Default")
      (node (ref "J8") (pin "1") (pinfunction "1_1") (pintype "passive+no_connect"))
    )
    (net (code "54") (name "unconnected-(J8-Pad5)") (class "Default")
      (node (ref "J8") (pin "5") (pinfunction "5_5") (pintype "passive+no_connect"))
    )
    (net (code "55") (name "unconnected-(J8-公共触点-Pad3)") (class "Default")
      (node (ref "J8") (pin "3") (pinfunction "公共触点_3") (pintype "passive+no_connect"))
    )
    (net (code "56") (name "unconnected-(J8-常开触点-Pad2)") (class "Default")
      (node (ref "J8") (pin "2") (pinfunction "常开触点_2") (pintype "passive+no_connect"))
    )
    (net (code "57") (name "unconnected-(J8-常闭触点-Pad4)") (class "Default")
      (node (ref "J8") (pin "4") (pinfunction "常闭触点_4") (pintype "passive+no_connect"))
    )
    (net (code "58") (name "unconnected-(J9-Pad1)") (class "Default")
      (node (ref "J9") (pin "1") (pinfunction "1_1") (pintype "passive+no_connect"))
    )
    (net (code "59") (name "unconnected-(J9-Pad5)") (class "Default")
      (node (ref "J9") (pin "5") (pinfunction "5_5") (pintype "passive+no_connect"))
    )
    (net (code "60") (name "unconnected-(J9-公共触点-Pad3)") (class "Default")
      (node (ref "J9") (pin "3") (pinfunction "公共触点_3") (pintype "passive+no_connect"))
    )
    (net (code "61") (name "unconnected-(J9-常开触点-Pad2)") (class "Default")
      (node (ref "J9") (pin "2") (pinfunction "常开触点_2") (pintype "passive+no_connect"))
    )
    (net (code "62") (name "unconnected-(J9-常闭触点-Pad4)") (class "Default")
      (node (ref "J9") (pin "4") (pinfunction "常闭触点_4") (pintype "passive+no_connect"))
    )
    (net (code "63") (name "unconnected-(R4-CW-Pad3)") (class "Default")
      (node (ref "R4") (pin "3") (pinfunction "CW_3") (pintype "passive"))
    )
    (net (code "64") (name "unconnected-(U1-TAB-Pad6)") (class "Default")
      (node (ref "U1") (pin "6") (pinfunction "TAB_6") (pintype "power_in+no_connect"))
    )
  )
)
